# design.net
KiCad netlist of a schematic drawn in Altium Designer
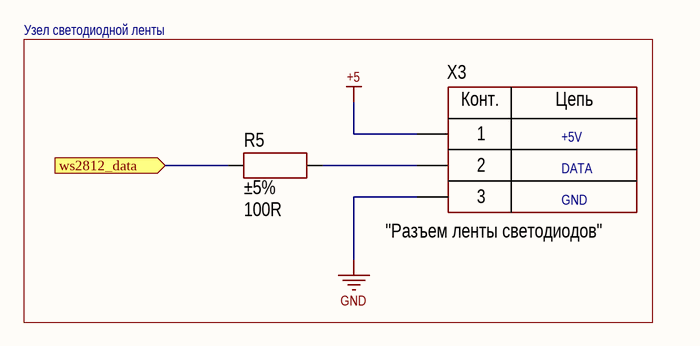
[diagram p0: Схема_узел_подключения светодиодной ленты.SchDoc]

(export (version "E")
  (design (tool "Eeschema 10.0.6"))
  (components
    (comp (ref "R5")
      (value "100R")
      (footprint "RES: 0603")
      (fields
        (field (name "MANUFACTURER") "Yageo")
        (field (name "PARTNUMBER") "RC0603JR-07100RL")
        (field (name "VALUEMANUFACTURERPARTNUMBER") "Resistor film, 100R, ±5%, 0603, 0.1W, -55...+125°C")
        (field (name "TOLERANCE") "±5%")
      )
      (libsource (lib "resistor") (part "Resistor_0603"))
    )
    (comp (ref "X3")
      (value "~")
      (footprint "CON: DG350-3.5-03P")
      (fields
        (field (name "MANUFACTURER") "Degson")
        (field (name "VALUEMANUFACTURERPARTNUMBER") "Terminal connector, 3pin, 3.5mm, 300VAC, 10A")
        (field (name "PARTNUMBER") "DG350-3.5-03P-14")
        (field (name "COMMENTTEXT") "\"Разъем ленты светодиодов\"")
      )
      (libsource (lib "connector") (part "Connector_terminal_3pin"))
    )
  )
  (nets
    (net (code "1") (name "+5") (class "Default")
      (node (ref "X3") (pin "1") (pinfunction "1_1") (pintype "passive"))
    )
    (net (code "2") (name "/ws2812_data") (class "Default")
      (node (ref "R5") (pin "1") (pinfunction "1_1") (pintype "passive"))
    )
    (net (code "3") (name "GND") (class "Default")
      (node (ref "X3") (pin "3") (pinfunction "3_3") (pintype "power_in"))
    )
    (net (code "4") (name "Net-(R5-Pad2)") (class "Default")
      (node (ref "R5") (pin "2") (pinfunction "2_2") (pintype "passive"))
      (node (ref "X3") (pin "2") (pinfunction "2_2") (pintype "passive"))
    )
  )
)
